# SD_Card_Led_Monitor.net
KiCad netlist of a schematic drawn in Altium Designer
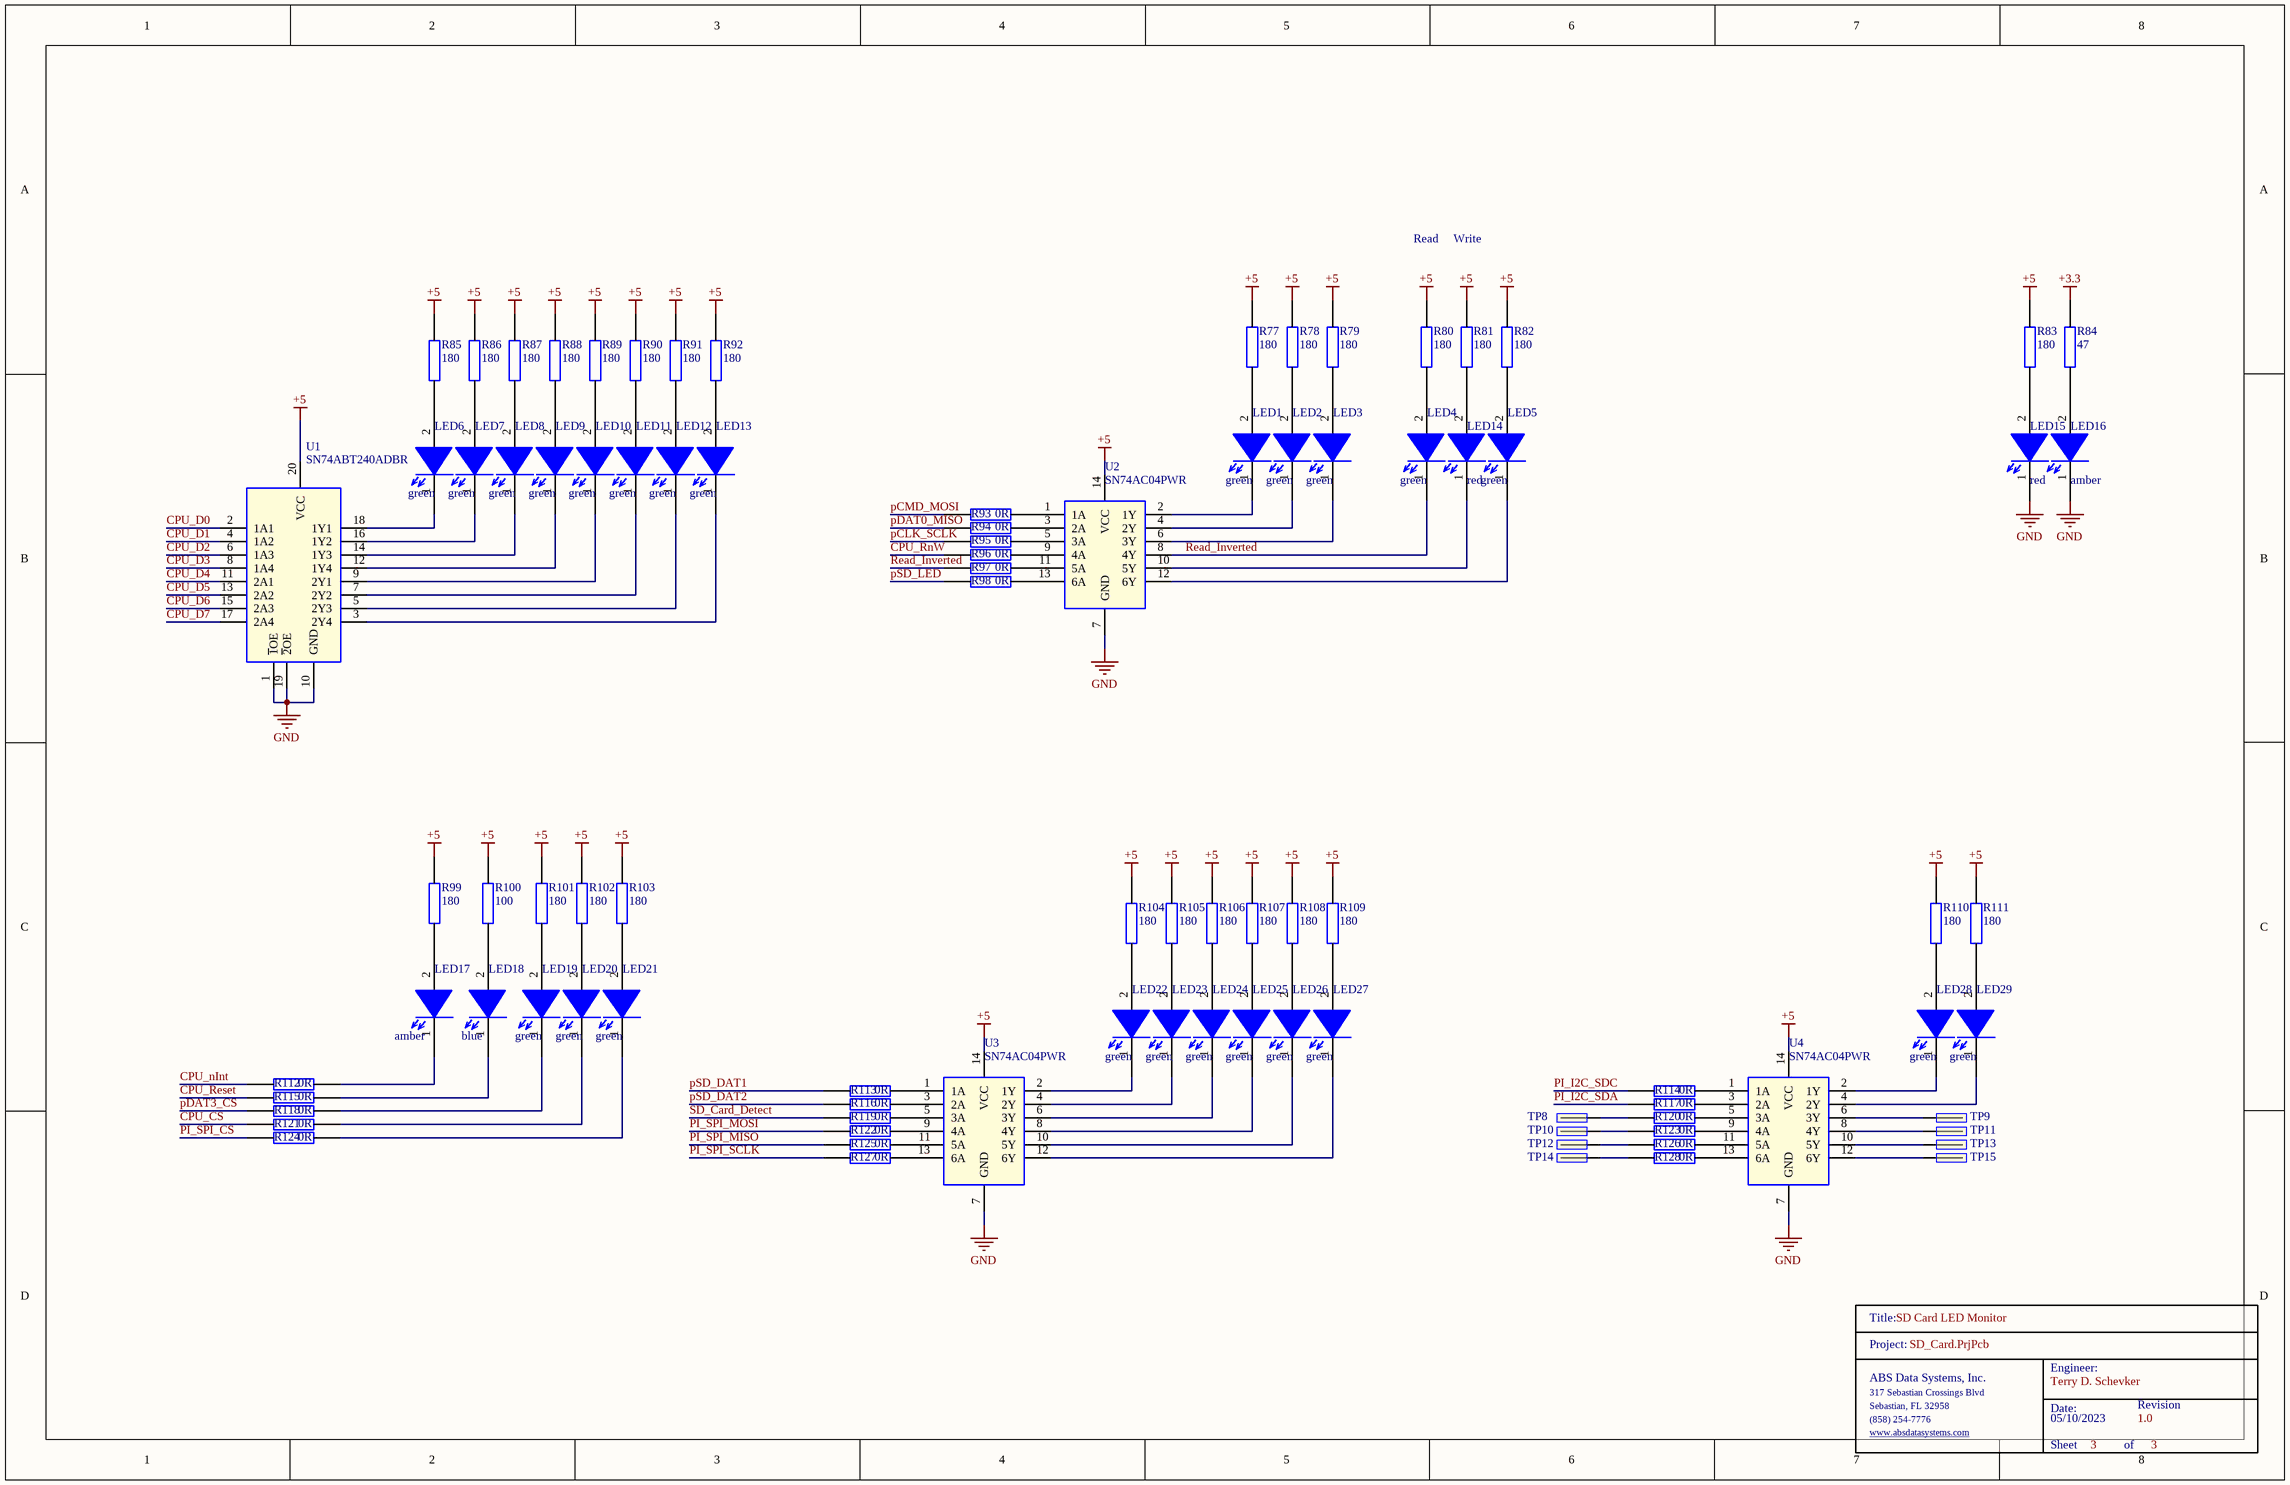
[diagram p0: SD_Card_Led_Monitor.SchDoc]

(export (version "E")
  (design (tool "Eeschema 10.0.6"))
  (components
    (comp (ref "LED1")
      (value "green")
      (footprint "0603_Diode")
      (description "Wurth Elektronik 0603 green")
      (fields
        (field (name "MANUFACTURER") "Wurth Electronics")
        (field (name "MANUFACTURER PART NUMBER") "150060GS75000")
      )
      (libsource (lib "Misc") (part "150060GS75000"))
    )
    (comp (ref "LED2")
      (value "green")
      (footprint "0603_Diode")
      (description "Wurth Elektronik 0603 green")
      (fields
        (field (name "MANUFACTURER") "Wurth Electronics")
        (field (name "MANUFACTURER PART NUMBER") "150060GS75000")
      )
      (libsource (lib "Misc") (part "150060GS75000"))
    )
    (comp (ref "LED3")
      (value "green")
      (footprint "0603_Diode")
      (description "Wurth Elektronik 0603 green")
      (fields
        (field (name "MANUFACTURER") "Wurth Electronics")
        (field (name "MANUFACTURER PART NUMBER") "150060GS75000")
      )
      (libsource (lib "Misc") (part "150060GS75000"))
    )
    (comp (ref "LED4")
      (value "green")
      (footprint "0603_Diode")
      (description "Wurth Elektronik 0603 green")
      (fields
        (field (name "MANUFACTURER") "Wurth Electronics")
        (field (name "MANUFACTURER PART NUMBER") "150060GS75000")
      )
      (libsource (lib "Misc") (part "150060GS75000"))
    )
    (comp (ref "LED5")
      (value "green")
      (footprint "0603_Diode")
      (description "Wurth Elektronik 0603 green")
      (fields
        (field (name "MANUFACTURER") "Wurth Electronics")
        (field (name "MANUFACTURER PART NUMBER") "150060GS75000")
      )
      (libsource (lib "Misc") (part "150060GS75000"))
    )
    (comp (ref "LED6")
      (value "green")
      (footprint "0603_Diode")
      (description "Wurth Elektronik 0603 green")
      (fields
        (field (name "MANUFACTURER") "Wurth Electronics")
        (field (name "MANUFACTURER PART NUMBER") "150060GS75000")
      )
      (libsource (lib "Misc") (part "150060GS75000"))
    )
    (comp (ref "LED7")
      (value "green")
      (footprint "0603_Diode")
      (description "Wurth Elektronik 0603 green")
      (fields
        (field (name "MANUFACTURER") "Wurth Electronics")
        (field (name "MANUFACTURER PART NUMBER") "150060GS75000")
      )
      (libsource (lib "Misc") (part "150060GS75000"))
    )
    (comp (ref "LED8")
      (value "green")
      (footprint "0603_Diode")
      (description "Wurth Elektronik 0603 green")
      (fields
        (field (name "MANUFACTURER") "Wurth Electronics")
        (field (name "MANUFACTURER PART NUMBER") "150060GS75000")
      )
      (libsource (lib "Misc") (part "150060GS75000"))
    )
    (comp (ref "LED9")
      (value "green")
      (footprint "0603_Diode")
      (description "Wurth Elektronik 0603 green")
      (fields
        (field (name "MANUFACTURER") "Wurth Electronics")
        (field (name "MANUFACTURER PART NUMBER") "150060GS75000")
      )
      (libsource (lib "Misc") (part "150060GS75000"))
    )
    (comp (ref "LED10")
      (value "green")
      (footprint "0603_Diode")
      (description "Wurth Elektronik 0603 green")
      (fields
        (field (name "MANUFACTURER") "Wurth Electronics")
        (field (name "MANUFACTURER PART NUMBER") "150060GS75000")
      )
      (libsource (lib "Misc") (part "150060GS75000"))
    )
    (comp (ref "LED11")
      (value "green")
      (footprint "0603_Diode")
      (description "Wurth Elektronik 0603 green")
      (fields
        (field (name "MANUFACTURER") "Wurth Electronics")
        (field (name "MANUFACTURER PART NUMBER") "150060GS75000")
      )
      (libsource (lib "Misc") (part "150060GS75000"))
    )
    (comp (ref "LED12")
      (value "green")
      (footprint "0603_Diode")
      (description "Wurth Elektronik 0603 green")
      (fields
        (field (name "MANUFACTURER") "Wurth Electronics")
        (field (name "MANUFACTURER PART NUMBER") "150060GS75000")
      )
      (libsource (lib "Misc") (part "150060GS75000"))
    )
    (comp (ref "LED13")
      (value "green")
      (footprint "0603_Diode")
      (description "Wurth Elektronik 0603 green")
      (fields
        (field (name "MANUFACTURER") "Wurth Electronics")
        (field (name "MANUFACTURER PART NUMBER") "150060GS75000")
      )
      (libsource (lib "Misc") (part "150060GS75000"))
    )
    (comp (ref "LED14")
      (value "red")
      (footprint "0603_Diode")
      (description "Wurth Elektronik 0603 red")
      (fields
        (field (name "MANUFACTURER") "Wurth Electronics")
        (field (name "MANUFACTURER PART NUMBER") "150060GS75000")
      )
      (libsource (lib "Misc") (part "150060RS75000"))
    )
    (comp (ref "LED15")
      (value "red")
      (footprint "0603_Diode")
      (description "Wurth Elektronik 0603 red")
      (fields
        (field (name "MANUFACTURER") "Wurth Electronics")
        (field (name "MANUFACTURER PART NUMBER") "150060GS75000")
      )
      (libsource (lib "Misc") (part "150060RS75000"))
    )
    (comp (ref "LED16")
      (value "amber")
      (footprint "0603_Diode")
      (description "Wurth Elektronik 0603 amber")
      (fields
        (field (name "MANUFACTURER") "Wurth Electronics")
        (field (name "MANUFACTURER PART NUMBER") "150060GS75000")
      )
      (libsource (lib "Misc") (part "150060AS75000"))
    )
    (comp (ref "LED17")
      (value "amber")
      (footprint "0603_Diode")
      (description "Wurth Elektronik 0603 amber")
      (fields
        (field (name "MANUFACTURER") "Wurth Electronics")
        (field (name "MANUFACTURER PART NUMBER") "150060GS75000")
      )
      (libsource (lib "Misc") (part "150060AS75000"))
    )
    (comp (ref "LED18")
      (value "blue")
      (footprint "0603_Diode")
      (description "Wurth Elektronik 0603 blue")
      (fields
        (field (name "MANUFACTURER") "Wurth Electronics")
        (field (name "MANUFACTURER PART NUMBER") "150060GS75000")
      )
      (libsource (lib "Misc") (part "150060BS75000"))
    )
    (comp (ref "LED19")
      (value "green")
      (footprint "0603_Diode")
      (description "Wurth Elektronik 0603 green")
      (fields
        (field (name "MANUFACTURER") "Wurth Electronics")
        (field (name "MANUFACTURER PART NUMBER") "150060GS75000")
      )
      (libsource (lib "Misc") (part "150060GS75000"))
    )
    (comp (ref "LED20")
      (value "green")
      (footprint "0603_Diode")
      (description "Wurth Elektronik 0603 green")
      (fields
        (field (name "MANUFACTURER") "Wurth Electronics")
        (field (name "MANUFACTURER PART NUMBER") "150060GS75000")
      )
      (libsource (lib "Misc") (part "150060GS75000"))
    )
    (comp (ref "LED21")
      (value "green")
      (footprint "0603_Diode")
      (description "Wurth Elektronik 0603 green")
      (fields
        (field (name "MANUFACTURER") "Wurth Electronics")
        (field (name "MANUFACTURER PART NUMBER") "150060GS75000")
      )
      (libsource (lib "Misc") (part "150060GS75000"))
    )
    (comp (ref "LED22")
      (value "green")
      (footprint "0603_Diode")
      (description "Wurth Elektronik 0603 green")
      (fields
        (field (name "MANUFACTURER") "Wurth Electronics")
        (field (name "MANUFACTURER PART NUMBER") "150060GS75000")
      )
      (libsource (lib "Misc") (part "150060GS75000"))
    )
    (comp (ref "LED23")
      (value "green")
      (footprint "0603_Diode")
      (description "Wurth Elektronik 0603 green")
      (fields
        (field (name "MANUFACTURER") "Wurth Electronics")
        (field (name "MANUFACTURER PART NUMBER") "150060GS75000")
      )
      (libsource (lib "Misc") (part "150060GS75000"))
    )
    (comp (ref "LED24")
      (value "green")
      (footprint "0603_Diode")
      (description "Wurth Elektronik 0603 green")
      (fields
        (field (name "MANUFACTURER") "Wurth Electronics")
        (field (name "MANUFACTURER PART NUMBER") "150060GS75000")
      )
      (libsource (lib "Misc") (part "150060GS75000"))
    )
    (comp (ref "LED25")
      (value "green")
      (footprint "0603_Diode")
      (description "Wurth Elektronik 0603 green")
      (fields
        (field (name "MANUFACTURER") "Wurth Electronics")
        (field (name "MANUFACTURER PART NUMBER") "150060GS75000")
      )
      (libsource (lib "Misc") (part "150060GS75000"))
    )
    (comp (ref "LED26")
      (value "green")
      (footprint "0603_Diode")
      (description "Wurth Elektronik 0603 green")
      (fields
        (field (name "MANUFACTURER") "Wurth Electronics")
        (field (name "MANUFACTURER PART NUMBER") "150060GS75000")
      )
      (libsource (lib "Misc") (part "150060GS75000"))
    )
    (comp (ref "LED27")
      (value "green")
      (footprint "0603_Diode")
      (description "Wurth Elektronik 0603 green")
      (fields
        (field (name "MANUFACTURER") "Wurth Electronics")
        (field (name "MANUFACTURER PART NUMBER") "150060GS75000")
      )
      (libsource (lib "Misc") (part "150060GS75000"))
    )
    (comp (ref "LED28")
      (value "green")
      (footprint "0603_Diode")
      (description "Wurth Elektronik 0603 green")
      (fields
        (field (name "MANUFACTURER") "Wurth Electronics")
        (field (name "MANUFACTURER PART NUMBER") "150060GS75000")
      )
      (libsource (lib "Misc") (part "150060GS75000"))
    )
    (comp (ref "LED29")
      (value "green")
      (footprint "0603_Diode")
      (description "Wurth Elektronik 0603 green")
      (fields
        (field (name "MANUFACTURER") "Wurth Electronics")
        (field (name "MANUFACTURER PART NUMBER") "150060GS75000")
      )
      (libsource (lib "Misc") (part "150060GS75000"))
    )
    (comp (ref "R77")
      (value "180")
      (footprint "0603")
      (description "YAGEO 0603 180 ohm")
      (fields
        (field (name "MOUSER PART NUMBER") "603-RC0603JR-070RL")
        (field (name "MANUFACTURER_PART_NUMBER") "RC0603JR-070RL")
      )
      (libsource (lib "Resistors") (part "RC0603FR-13180RL"))
    )
    (comp (ref "R78")
      (value "180")
      (footprint "0603")
      (description "YAGEO 0603 180 ohm")
      (fields
        (field (name "MOUSER PART NUMBER") "603-RC0603JR-070RL")
        (field (name "MANUFACTURER_PART_NUMBER") "RC0603JR-070RL")
      )
      (libsource (lib "Resistors") (part "RC0603FR-13180RL"))
    )
    (comp (ref "R79")
      (value "180")
      (footprint "0603")
      (description "YAGEO 0603 180 ohm")
      (fields
        (field (name "MOUSER PART NUMBER") "603-RC0603JR-070RL")
        (field (name "MANUFACTURER_PART_NUMBER") "RC0603JR-070RL")
      )
      (libsource (lib "Resistors") (part "RC0603FR-13180RL"))
    )
    (comp (ref "R80")
      (value "180")
      (footprint "0603")
      (description "YAGEO 0603 180 ohm")
      (fields
        (field (name "MOUSER PART NUMBER") "603-RC0603JR-070RL")
        (field (name "MANUFACTURER_PART_NUMBER") "RC0603JR-070RL")
      )
      (libsource (lib "Resistors") (part "RC0603FR-13180RL"))
    )
    (comp (ref "R81")
      (value "180")
      (footprint "0603")
      (description "YAGEO 0603 180 ohm")
      (fields
        (field (name "MOUSER PART NUMBER") "603-RC0603JR-070RL")
        (field (name "MANUFACTURER_PART_NUMBER") "RC0603JR-070RL")
      )
      (libsource (lib "Resistors") (part "RC0603FR-13180RL"))
    )
    (comp (ref "R82")
      (value "180")
      (footprint "0603")
      (description "YAGEO 0603 180 ohm")
      (fields
        (field (name "MOUSER PART NUMBER") "603-RC0603JR-070RL")
        (field (name "MANUFACTURER_PART_NUMBER") "RC0603JR-070RL")
      )
      (libsource (lib "Resistors") (part "RC0603FR-13180RL"))
    )
    (comp (ref "R83")
      (value "180")
      (footprint "0603")
      (description "YAGEO 0603 180 ohm")
      (fields
        (field (name "MOUSER PART NUMBER") "603-RC0603JR-070RL")
        (field (name "MANUFACTURER_PART_NUMBER") "RC0603JR-070RL")
      )
      (libsource (lib "Resistors") (part "RC0603FR-13180RL"))
    )
    (comp (ref "R84")
      (value "47")
      (footprint "0603")
      (description "YAGEO 0603 47")
      (fields
        (field (name "MOUSER PART NUMBER") "603-RC0603JR-070RL")
        (field (name "MANUFACTURER_PART_NUMBER") "RC0603JR-070RL")
      )
      (libsource (lib "Resistors") (part "RC0603FR-0747KL"))
    )
    (comp (ref "R85")
      (value "180")
      (footprint "0603")
      (description "YAGEO 0603 180 ohm")
      (fields
        (field (name "MOUSER PART NUMBER") "603-RC0603JR-070RL")
        (field (name "MANUFACTURER_PART_NUMBER") "RC0603JR-070RL")
      )
      (libsource (lib "Resistors") (part "RC0603FR-13180RL"))
    )
    (comp (ref "R86")
      (value "180")
      (footprint "0603")
      (description "YAGEO 0603 180 ohm")
      (fields
        (field (name "MOUSER PART NUMBER") "603-RC0603JR-070RL")
        (field (name "MANUFACTURER_PART_NUMBER") "RC0603JR-070RL")
      )
      (libsource (lib "Resistors") (part "RC0603FR-13180RL"))
    )
    (comp (ref "R87")
      (value "180")
      (footprint "0603")
      (description "YAGEO 0603 180 ohm")
      (fields
        (field (name "MOUSER PART NUMBER") "603-RC0603JR-070RL")
        (field (name "MANUFACTURER_PART_NUMBER") "RC0603JR-070RL")
      )
      (libsource (lib "Resistors") (part "RC0603FR-13180RL"))
    )
    (comp (ref "R88")
      (value "180")
      (footprint "0603")
      (description "YAGEO 0603 180 ohm")
      (fields
        (field (name "MOUSER PART NUMBER") "603-RC0603JR-070RL")
        (field (name "MANUFACTURER_PART_NUMBER") "RC0603JR-070RL")
      )
      (libsource (lib "Resistors") (part "RC0603FR-13180RL"))
    )
    (comp (ref "R89")
      (value "180")
      (footprint "0603")
      (description "YAGEO 0603 180 ohm")
      (fields
        (field (name "MOUSER PART NUMBER") "603-RC0603JR-070RL")
        (field (name "MANUFACTURER_PART_NUMBER") "RC0603JR-070RL")
      )
      (libsource (lib "Resistors") (part "RC0603FR-13180RL"))
    )
    (comp (ref "R90")
      (value "180")
      (footprint "0603")
      (description "YAGEO 0603 180 ohm")
      (fields
        (field (name "MOUSER PART NUMBER") "603-RC0603JR-070RL")
        (field (name "MANUFACTURER_PART_NUMBER") "RC0603JR-070RL")
      )
      (libsource (lib "Resistors") (part "RC0603FR-13180RL"))
    )
    (comp (ref "R91")
      (value "180")
      (footprint "0603")
      (description "YAGEO 0603 180 ohm")
      (fields
        (field (name "MOUSER PART NUMBER") "603-RC0603JR-070RL")
        (field (name "MANUFACTURER_PART_NUMBER") "RC0603JR-070RL")
      )
      (libsource (lib "Resistors") (part "RC0603FR-13180RL"))
    )
    (comp (ref "R92")
      (value "180")
      (footprint "0603")
      (description "YAGEO 0603 180 ohm")
      (fields
        (field (name "MOUSER PART NUMBER") "603-RC0603JR-070RL")
        (field (name "MANUFACTURER_PART_NUMBER") "RC0603JR-070RL")
      )
      (libsource (lib "Resistors") (part "RC0603FR-13180RL"))
    )
    (comp (ref "R93")
      (value "0R")
      (footprint "0603")
      (description "YAGEO 0603 0 ohm")
      (fields
        (field (name "MOUSER PART NUMBER") "603-RC0603JR-070RL")
        (field (name "MANUFACTURER_PART_NUMBER") "RC0603JR-070RL")
      )
      (libsource (lib "Resistors") (part "RC0603JR-070RL"))
    )
    (comp (ref "R94")
      (value "0R")
      (footprint "0603")
      (description "YAGEO 0603 0 ohm")
      (fields
        (field (name "MOUSER PART NUMBER") "603-RC0603JR-070RL")
        (field (name "MANUFACTURER_PART_NUMBER") "RC0603JR-070RL")
      )
      (libsource (lib "Resistors") (part "RC0603JR-070RL"))
    )
    (comp (ref "R95")
      (value "0R")
      (footprint "0603")
      (description "YAGEO 0603 0 ohm")
      (fields
        (field (name "MOUSER PART NUMBER") "603-RC0603JR-070RL")
        (field (name "MANUFACTURER_PART_NUMBER") "RC0603JR-070RL")
      )
      (libsource (lib "Resistors") (part "RC0603JR-070RL"))
    )
    (comp (ref "R96")
      (value "0R")
      (footprint "0603")
      (description "YAGEO 0603 0 ohm")
      (fields
        (field (name "MOUSER PART NUMBER") "603-RC0603JR-070RL")
        (field (name "MANUFACTURER_PART_NUMBER") "RC0603JR-070RL")
      )
      (libsource (lib "Resistors") (part "RC0603JR-070RL"))
    )
    (comp (ref "R97")
      (value "0R")
      (footprint "0603")
      (description "YAGEO 0603 0 ohm")
      (fields
        (field (name "MOUSER PART NUMBER") "603-RC0603JR-070RL")
        (field (name "MANUFACTURER_PART_NUMBER") "RC0603JR-070RL")
      )
      (libsource (lib "Resistors") (part "RC0603JR-070RL"))
    )
    (comp (ref "R98")
      (value "0R")
      (footprint "0603")
      (description "YAGEO 0603 0 ohm")
      (fields
        (field (name "MOUSER PART NUMBER") "603-RC0603JR-070RL")
        (field (name "MANUFACTURER_PART_NUMBER") "RC0603JR-070RL")
      )
      (libsource (lib "Resistors") (part "RC0603JR-070RL"))
    )
    (comp (ref "R99")
      (value "180")
      (footprint "0603")
      (description "YAGEO 0603 180 ohm")
      (fields
        (field (name "MOUSER PART NUMBER") "603-RC0603JR-070RL")
        (field (name "MANUFACTURER_PART_NUMBER") "RC0603JR-070RL")
      )
      (libsource (lib "Resistors") (part "RC0603FR-13180RL"))
    )
    (comp (ref "R100")
      (value "100")
      (footprint "0603")
      (description "YAGEO 0603 100 ohm")
      (fields
        (field (name "MOUSER PART NUMBER") "603-RC0603JR-070RL")
        (field (name "MANUFACTURER_PART_NUMBER") "RC0603JR-070RL")
      )
      (libsource (lib "Resistors") (part "RC0603FR-10100RL"))
    )
    (comp (ref "R101")
      (value "180")
      (footprint "0603")
      (description "YAGEO 0603 180 ohm")
      (fields
        (field (name "MOUSER PART NUMBER") "603-RC0603JR-070RL")
        (field (name "MANUFACTURER_PART_NUMBER") "RC0603JR-070RL")
      )
      (libsource (lib "Resistors") (part "RC0603FR-13180RL"))
    )
    (comp (ref "R102")
      (value "180")
      (footprint "0603")
      (description "YAGEO 0603 180 ohm")
      (fields
        (field (name "MOUSER PART NUMBER") "603-RC0603JR-070RL")
        (field (name "MANUFACTURER_PART_NUMBER") "RC0603JR-070RL")
      )
      (libsource (lib "Resistors") (part "RC0603FR-13180RL"))
    )
    (comp (ref "R103")
      (value "180")
      (footprint "0603")
      (description "YAGEO 0603 180 ohm")
      (fields
        (field (name "MOUSER PART NUMBER") "603-RC0603JR-070RL")
        (field (name "MANUFACTURER_PART_NUMBER") "RC0603JR-070RL")
      )
      (libsource (lib "Resistors") (part "RC0603FR-13180RL"))
    )
    (comp (ref "R104")
      (value "180")
      (footprint "0603")
      (description "YAGEO 0603 180 ohm")
      (fields
        (field (name "MOUSER PART NUMBER") "603-RC0603JR-070RL")
        (field (name "MANUFACTURER_PART_NUMBER") "RC0603JR-070RL")
      )
      (libsource (lib "Resistors") (part "RC0603FR-13180RL"))
    )
    (comp (ref "R105")
      (value "180")
      (footprint "0603")
      (description "YAGEO 0603 180 ohm")
      (fields
        (field (name "MOUSER PART NUMBER") "603-RC0603JR-070RL")
        (field (name "MANUFACTURER_PART_NUMBER") "RC0603JR-070RL")
      )
      (libsource (lib "Resistors") (part "RC0603FR-13180RL"))
    )
    (comp (ref "R106")
      (value "180")
      (footprint "0603")
      (description "YAGEO 0603 180 ohm")
      (fields
        (field (name "MOUSER PART NUMBER") "603-RC0603JR-070RL")
        (field (name "MANUFACTURER_PART_NUMBER") "RC0603JR-070RL")
      )
      (libsource (lib "Resistors") (part "RC0603FR-13180RL"))
    )
    (comp (ref "R107")
      (value "180")
      (footprint "0603")
      (description "YAGEO 0603 180 ohm")
      (fields
        (field (name "MOUSER PART NUMBER") "603-RC0603JR-070RL")
        (field (name "MANUFACTURER_PART_NUMBER") "RC0603JR-070RL")
      )
      (libsource (lib "Resistors") (part "RC0603FR-13180RL"))
    )
    (comp (ref "R108")
      (value "180")
      (footprint "0603")
      (description "YAGEO 0603 180 ohm")
      (fields
        (field (name "MOUSER PART NUMBER") "603-RC0603JR-070RL")
        (field (name "MANUFACTURER_PART_NUMBER") "RC0603JR-070RL")
      )
      (libsource (lib "Resistors") (part "RC0603FR-13180RL"))
    )
    (comp (ref "R109")
      (value "180")
      (footprint "0603")
      (description "YAGEO 0603 180 ohm")
      (fields
        (field (name "MOUSER PART NUMBER") "603-RC0603JR-070RL")
        (field (name "MANUFACTURER_PART_NUMBER") "RC0603JR-070RL")
      )
      (libsource (lib "Resistors") (part "RC0603FR-13180RL"))
    )
    (comp (ref "R110")
      (value "180")
      (footprint "0603")
      (description "YAGEO 0603 180 ohm")
      (fields
        (field (name "MOUSER PART NUMBER") "603-RC0603JR-070RL")
        (field (name "MANUFACTURER_PART_NUMBER") "RC0603JR-070RL")
      )
      (libsource (lib "Resistors") (part "RC0603FR-13180RL"))
    )
    (comp (ref "R111")
      (value "180")
      (footprint "0603")
      (description "YAGEO 0603 180 ohm")
      (fields
        (field (name "MOUSER PART NUMBER") "603-RC0603JR-070RL")
        (field (name "MANUFACTURER_PART_NUMBER") "RC0603JR-070RL")
      )
      (libsource (lib "Resistors") (part "RC0603FR-13180RL"))
    )
    (comp (ref "R112")
      (value "0R")
      (footprint "0603")
      (description "YAGEO 0603 0 ohm")
      (fields
        (field (name "MOUSER PART NUMBER") "603-RC0603JR-070RL")
        (field (name "MANUFACTURER_PART_NUMBER") "RC0603JR-070RL")
      )
      (libsource (lib "Resistors") (part "RC0603JR-070RL"))
    )
    (comp (ref "R113")
      (value "0R")
      (footprint "0603")
      (description "YAGEO 0603 0 ohm")
      (fields
        (field (name "MOUSER PART NUMBER") "603-RC0603JR-070RL")
        (field (name "MANUFACTURER_PART_NUMBER") "RC0603JR-070RL")
      )
      (libsource (lib "Resistors") (part "RC0603JR-070RL"))
    )
    (comp (ref "R114")
      (value "0R")
      (footprint "0603")
      (description "YAGEO 0603 0 ohm")
      (fields
        (field (name "MOUSER PART NUMBER") "603-RC0603JR-070RL")
        (field (name "MANUFACTURER_PART_NUMBER") "RC0603JR-070RL")
      )
      (libsource (lib "Resistors") (part "RC0603JR-070RL"))
    )
    (comp (ref "R115")
      (value "0R")
      (footprint "0603")
      (description "YAGEO 0603 0 ohm")
      (fields
        (field (name "MOUSER PART NUMBER") "603-RC0603JR-070RL")
        (field (name "MANUFACTURER_PART_NUMBER") "RC0603JR-070RL")
      )
      (libsource (lib "Resistors") (part "RC0603JR-070RL"))
    )
    (comp (ref "R116")
      (value "0R")
      (footprint "0603")
      (description "YAGEO 0603 0 ohm")
      (fields
        (field (name "MOUSER PART NUMBER") "603-RC0603JR-070RL")
        (field (name "MANUFACTURER_PART_NUMBER") "RC0603JR-070RL")
      )
      (libsource (lib "Resistors") (part "RC0603JR-070RL"))
    )
    (comp (ref "R117")
      (value "0R")
      (footprint "0603")
      (description "YAGEO 0603 0 ohm")
      (fields
        (field (name "MOUSER PART NUMBER") "603-RC0603JR-070RL")
        (field (name "MANUFACTURER_PART_NUMBER") "RC0603JR-070RL")
      )
      (libsource (lib "Resistors") (part "RC0603JR-070RL"))
    )
    (comp (ref "R118")
      (value "0R")
      (footprint "0603")
      (description "YAGEO 0603 0 ohm")
      (fields
        (field (name "MOUSER PART NUMBER") "603-RC0603JR-070RL")
        (field (name "MANUFACTURER_PART_NUMBER") "RC0603JR-070RL")
      )
      (libsource (lib "Resistors") (part "RC0603JR-070RL"))
    )
    (comp (ref "R119")
      (value "0R")
      (footprint "0603")
      (description "YAGEO 0603 0 ohm")
      (fields
        (field (name "MOUSER PART NUMBER") "603-RC0603JR-070RL")
        (field (name "MANUFACTURER_PART_NUMBER") "RC0603JR-070RL")
      )
      (libsource (lib "Resistors") (part "RC0603JR-070RL"))
    )
    (comp (ref "R120")
      (value "0R")
      (footprint "0603")
      (description "YAGEO 0603 0 ohm")
      (fields
        (field (name "MOUSER PART NUMBER") "603-RC0603JR-070RL")
        (field (name "MANUFACTURER_PART_NUMBER") "RC0603JR-070RL")
      )
      (libsource (lib "Resistors") (part "RC0603JR-070RL"))
    )
    (comp (ref "R121")
      (value "0R")
      (footprint "0603")
      (description "YAGEO 0603 0 ohm")
      (fields
        (field (name "MOUSER PART NUMBER") "603-RC0603JR-070RL")
        (field (name "MANUFACTURER_PART_NUMBER") "RC0603JR-070RL")
      )
      (libsource (lib "Resistors") (part "RC0603JR-070RL"))
    )
    (comp (ref "R122")
      (value "0R")
      (footprint "0603")
      (description "YAGEO 0603 0 ohm")
      (fields
        (field (name "MOUSER PART NUMBER") "603-RC0603JR-070RL")
        (field (name "MANUFACTURER_PART_NUMBER") "RC0603JR-070RL")
      )
      (libsource (lib "Resistors") (part "RC0603JR-070RL"))
    )
    (comp (ref "R123")
      (value "0R")
      (footprint "0603")
      (description "YAGEO 0603 0 ohm")
      (fields
        (field (name "MOUSER PART NUMBER") "603-RC0603JR-070RL")
        (field (name "MANUFACTURER_PART_NUMBER") "RC0603JR-070RL")
      )
      (libsource (lib "Resistors") (part "RC0603JR-070RL"))
    )
    (comp (ref "R124")
      (value "0R")
      (footprint "0603")
      (description "YAGEO 0603 0 ohm")
      (fields
        (field (name "MOUSER PART NUMBER") "603-RC0603JR-070RL")
        (field (name "MANUFACTURER_PART_NUMBER") "RC0603JR-070RL")
      )
      (libsource (lib "Resistors") (part "RC0603JR-070RL"))
    )
    (comp (ref "R125")
      (value "0R")
      (footprint "0603")
      (description "YAGEO 0603 0 ohm")
      (fields
        (field (name "MOUSER PART NUMBER") "603-RC0603JR-070RL")
        (field (name "MANUFACTURER_PART_NUMBER") "RC0603JR-070RL")
      )
      (libsource (lib "Resistors") (part "RC0603JR-070RL"))
    )
    (comp (ref "R126")
      (value "0R")
      (footprint "0603")
      (description "YAGEO 0603 0 ohm")
      (fields
        (field (name "MOUSER PART NUMBER") "603-RC0603JR-070RL")
        (field (name "MANUFACTURER_PART_NUMBER") "RC0603JR-070RL")
      )
      (libsource (lib "Resistors") (part "RC0603JR-070RL"))
    )
    (comp (ref "R127")
      (value "0R")
      (footprint "0603")
      (description "YAGEO 0603 0 ohm")
      (fields
        (field (name "MOUSER PART NUMBER") "603-RC0603JR-070RL")
        (field (name "MANUFACTURER_PART_NUMBER") "RC0603JR-070RL")
      )
      (libsource (lib "Resistors") (part "RC0603JR-070RL"))
    )
    (comp (ref "R128")
      (value "0R")
      (footprint "0603")
      (description "YAGEO 0603 0 ohm")
      (fields
        (field (name "MOUSER PART NUMBER") "603-RC0603JR-070RL")
        (field (name "MANUFACTURER_PART_NUMBER") "RC0603JR-070RL")
      )
      (libsource (lib "Resistors") (part "RC0603JR-070RL"))
    )
    (comp (ref "TitleBlock_3") (value "TitleBlock") (libsource (lib "Misc") (part "TitleBlock")))
    (comp (ref "TP8")
      (value "TP")
      (footprint "TP")
      (fields
        (field (name "MANUFACTURER") "Samtec")
        (field (name "MANUFACTURER PART NUMBER") "TST-105-01-G-D")
      )
      (libsource (lib "") (part "TP_1"))
    )
    (comp (ref "TP9")
      (value "TP")
      (footprint "TP")
      (fields
        (field (name "MANUFACTURER") "Samtec")
        (field (name "MANUFACTURER PART NUMBER") "TST-105-01-G-D")
      )
      (libsource (lib "Misc") (part "TP"))
    )
    (comp (ref "TP10")
      (value "TP")
      (footprint "TP")
      (fields
        (field (name "MANUFACTURER") "Samtec")
        (field (name "MANUFACTURER PART NUMBER") "TST-105-01-G-D")
      )
      (libsource (lib "") (part "TP_1"))
    )
    (comp (ref "TP11")
      (value "TP")
      (footprint "TP")
      (fields
        (field (name "MANUFACTURER") "Samtec")
        (field (name "MANUFACTURER PART NUMBER") "TST-105-01-G-D")
      )
      (libsource (lib "Misc") (part "TP"))
    )
    (comp (ref "TP12")
      (value "TP")
      (footprint "TP")
      (fields
        (field (name "MANUFACTURER") "Samtec")
        (field (name "MANUFACTURER PART NUMBER") "TST-105-01-G-D")
      )
      (libsource (lib "") (part "TP_1"))
    )
    (comp (ref "TP13")
      (value "TP")
      (footprint "TP")
      (fields
        (field (name "MANUFACTURER") "Samtec")
        (field (name "MANUFACTURER PART NUMBER") "TST-105-01-G-D")
      )
      (libsource (lib "Misc") (part "TP"))
    )
    (comp (ref "TP14")
      (value "TP")
      (footprint "TP")
      (fields
        (field (name "MANUFACTURER") "Samtec")
        (field (name "MANUFACTURER PART NUMBER") "TST-105-01-G-D")
      )
      (libsource (lib "") (part "TP_1"))
    )
    (comp (ref "TP15")
      (value "TP")
      (footprint "TP")
      (fields
        (field (name "MANUFACTURER") "Samtec")
        (field (name "MANUFACTURER PART NUMBER") "TST-105-01-G-D")
      )
      (libsource (lib "Misc") (part "TP"))
    )
    (comp (ref "U1")
      (value "SN74ABT240ADBR")
      (footprint "SOP65P780X200-20N")
      (description "Octal Buffers/Drivers With 3-State Outputs")
      (fields (field (name "MOUSER PART NUMBER") "595-SN74ABT240ADBR"))
      (libsource (lib "Logic") (part "SN74ABT240ADBR"))
    )
    (comp (ref "U2")
      (value "SN74AC04PWR")
      (footprint "SOP65P640X120-14N")
      (description "Hex Inverters")
      (fields (field (name "MOUSER PART NUMBER") "595-SN74AC04PWR"))
      (libsource (lib "Logic") (part "SN74AC04PWR"))
    )
    (comp (ref "U3")
      (value "SN74AC04PWR")
      (footprint "SOP65P640X120-14N")
      (description "Hex Inverters")
      (fields (field (name "MOUSER PART NUMBER") "595-SN74AC04PWR"))
      (libsource (lib "Logic") (part "SN74AC04PWR"))
    )
    (comp (ref "U4")
      (value "SN74AC04PWR")
      (footprint "SOP65P640X120-14N")
      (description "Hex Inverters")
      (fields (field (name "MOUSER PART NUMBER") "595-SN74AC04PWR"))
      (libsource (lib "Logic") (part "SN74AC04PWR"))
    )
  )
  (nets
    (net (code "1") (name "+3.3") (class "Default")
      (node (ref "R84") (pin "1") (pinfunction "1_1") (pintype "passive"))
    )
    (net (code "2") (name "+5") (class "Default")
      (node (ref "R100") (pin "1") (pinfunction "1_1") (pintype "passive"))
      (node (ref "R101") (pin "2") (pinfunction "2_2") (pintype "passive"))
      (node (ref "R102") (pin "2") (pinfunction "2_2") (pintype "passive"))
      (node (ref "R103") (pin "2") (pinfunction "2_2") (pintype "passive"))
      (node (ref "R104") (pin "2") (pinfunction "2_2") (pintype "passive"))
      (node (ref "R105") (pin "2") (pinfunction "2_2") (pintype "passive"))
      (node (ref "R106") (pin "2") (pinfunction "2_2") (pintype "passive"))
      (node (ref "R107") (pin "2") (pinfunction "2_2") (pintype "passive"))
      (node (ref "R108") (pin "2") (pinfunction "2_2") (pintype "passive"))
      (node (ref "R109") (pin "2") (pinfunction "2_2") (pintype "passive"))
      (node (ref "R110") (pin "2") (pinfunction "2_2") (pintype "passive"))
      (node (ref "R111") (pin "2") (pinfunction "2_2") (pintype "passive"))
      (node (ref "R77") (pin "2") (pinfunction "2_2") (pintype "passive"))
      (node (ref "R78") (pin "2") (pinfunction "2_2") (pintype "passive"))
      (node (ref "R79") (pin "2") (pinfunction "2_2") (pintype "passive"))
      (node (ref "R80") (pin "2") (pinfunction "2_2") (pintype "passive"))
      (node (ref "R81") (pin "2") (pinfunction "2_2") (pintype "passive"))
      (node (ref "R82") (pin "2") (pinfunction "2_2") (pintype "passive"))
      (node (ref "R83") (pin "2") (pinfunction "2_2") (pintype "passive"))
      (node (ref "R85") (pin "2") (pinfunction "2_2") (pintype "passive"))
      (node (ref "R86") (pin "2") (pinfunction "2_2") (pintype "passive"))
      (node (ref "R87") (pin "2") (pinfunction "2_2") (pintype "passive"))
      (node (ref "R88") (pin "2") (pinfunction "2_2") (pintype "passive"))
      (node (ref "R89") (pin "2") (pinfunction "2_2") (pintype "passive"))
      (node (ref "R90") (pin "2") (pinfunction "2_2") (pintype "passive"))
      (node (ref "R91") (pin "2") (pinfunction "2_2") (pintype "passive"))
      (node (ref "R92") (pin "2") (pinfunction "2_2") (pintype "passive"))
      (node (ref "R99") (pin "2") (pinfunction "2_2") (pintype "passive"))
      (node (ref "U1") (pin "20") (pinfunction "VCC_20") (pintype "passive"))
      (node (ref "U2") (pin "14") (pinfunction "VCC_14") (pintype "passive"))
      (node (ref "U3") (pin "14") (pinfunction "VCC_14") (pintype "passive"))
      (node (ref "U4") (pin "14") (pinfunction "VCC_14") (pintype "passive"))
    )
    (net (code "3") (name "/CPU_CS") (class "Default")
      (node (ref "R121") (pin "1") (pinfunction "1_1") (pintype "passive"))
    )
    (net (code "4") (name "/CPU_D0") (class "Default")
      (node (ref "U1") (pin "2") (pinfunction "1A1_2") (pintype "passive"))
    )
    (net (code "5") (name "/CPU_D1") (class "Default")
      (node (ref "U1") (pin "4") (pinfunction "1A2_4") (pintype "passive"))
    )
    (net (code "6") (name "/CPU_D2") (class "Default")
      (node (ref "U1") (pin "6") (pinfunction "1A3_6") (pintype "passive"))
    )
    (net (code "7") (name "/CPU_D3") (class "Default")
      (node (ref "U1") (pin "8") (pinfunction "1A4_8") (pintype "passive"))
    )
    (net (code "8") (name "/CPU_D4") (class "Default")
      (node (ref "U1") (pin "11") (pinfunction "2A1_11") (pintype "passive"))
    )
    (net (code "9") (name "/CPU_D5") (class "Default")
      (node (ref "U1") (pin "13") (pinfunction "2A2_13") (pintype "passive"))
    )
    (net (code "10") (name "/CPU_D6") (class "Default")
      (node (ref "U1") (pin "15") (pinfunction "2A3_15") (pintype "passive"))
    )
    (net (code "11") (name "/CPU_D7") (class "Default")
      (node (ref "U1") (pin "17") (pinfunction "2A4_17") (pintype "passive"))
    )
    (net (code "12") (name "/CPU_Reset") (class "Default")
      (node (ref "R115") (pin "1") (pinfunction "1_1") (pintype "passive"))
    )
    (net (code "13") (name "/CPU_RnW") (class "Default")
      (node (ref "R96") (pin "1") (pinfunction "1_1") (pintype "passive"))
    )
    (net (code "14") (name "/CPU_nInt") (class "Default")
      (node (ref "R112") (pin "1") (pinfunction "1_1") (pintype "passive"))
    )
    (net (code "15") (name "/PI_I2C_SDA") (class "Default")
      (node (ref "R117") (pin "1") (pinfunction "1_1") (pintype "passive"))
    )
    (net (code "16") (name "/PI_I2C_SDC") (class "Default")
      (node (ref "R114") (pin "1") (pinfunction "1_1") (pintype "passive"))
    )
    (net (code "17") (name "/PI_SPI_CS") (class "Default")
      (node (ref "R124") (pin "1") (pinfunction "1_1") (pintype "passive"))
    )
    (net (code "18") (name "/PI_SPI_MISO") (class "Default")
      (node (ref "R125") (pin "1") (pinfunction "1_1") (pintype "passive"))
    )
    (net (code "19") (name "/PI_SPI_MOSI") (class "Default")
      (node (ref "R122") (pin "1") (pinfunction "1_1") (pintype "passive"))
    )
    (net (code "20") (name "/PI_SPI_SCLK") (class "Default")
      (node (ref "R127") (pin "1") (pinfunction "1_1") (pintype "passive"))
    )
    (net (code "21") (name "/Read_Inverted") (class "Default")
      (node (ref "LED4") (pin "1") (pinfunction "K_1") (pintype "passive"))
      (node (ref "R97") (pin "1") (pinfunction "1_1") (pintype "passive"))
      (node (ref "U2") (pin "8") (pinfunction "4Y_8") (pintype "passive"))
    )
    (net (code "22") (name "/SD_Card_Detect") (class "Default")
      (node (ref "R119") (pin "1") (pinfunction "1_1") (pintype "passive"))
    )
    (net (code "23") (name "/pCLK_SCLK") (class "Default")
      (node (ref "R95") (pin "1") (pinfunction "1_1") (pintype "passive"))
    )
    (net (code "24") (name "/pCMD_MOSI") (class "Default")
      (node (ref "R93") (pin "1") (pinfunction "1_1") (pintype "passive"))
    )
    (net (code "25") (name "/pDAT0_MISO") (class "Default")
      (node (ref "R94") (pin "1") (pinfunction "1_1") (pintype "passive"))
    )
    (net (code "26") (name "/pDAT3_CS") (class "Default")
      (node (ref "R118") (pin "1") (pinfunction "1_1") (pintype "passive"))
    )
    (net (code "27") (name "/pSD_DAT1") (class "Default")
      (node (ref "R113") (pin "1") (pinfunction "1_1") (pintype "passive"))
    )
    (net (code "28") (name "/pSD_DAT2") (class "Default")
      (node (ref "R116") (pin "1") (pinfunction "1_1") (pintype "passive"))
    )
    (net (code "29") (name "/pSD_LED") (class "Default")
      (node (ref "R98") (pin "1") (pinfunction "1_1") (pintype "passive"))
    )
    (net (code "30") (name "GND") (class "Default")
      (node (ref "LED15") (pin "1") (pinfunction "K_1") (pintype "passive"))
      (node (ref "LED16") (pin "1") (pinfunction "K_1") (pintype "passive"))
      (node (ref "U1") (pin "1") (pinfunction "~{1}OE_1") (pintype "passive"))
      (node (ref "U1") (pin "10") (pinfunction "GND_10") (pintype "passive"))
      (node (ref "U1") (pin "19") (pinfunction "~{2}OE_19") (pintype "passive"))
      (node (ref "U2") (pin "7") (pinfunction "GND_7") (pintype "passive"))
      (node (ref "U3") (pin "7") (pinfunction "GND_7") (pintype "passive"))
      (node (ref "U4") (pin "7") (pinfunction "GND_7") (pintype "passive"))
    )
    (net (code "31") (name "Net-(LED1-A)") (class "Default")
      (node (ref "LED1") (pin "2") (pinfunction "A_2") (pintype "passive"))
      (node (ref "R77") (pin "1") (pinfunction "1_1") (pintype "passive"))
    )
    (net (code "32") (name "Net-(LED1-K)") (class "Default")
      (node (ref "LED1") (pin "1") (pinfunction "K_1") (pintype "passive"))
      (node (ref "U2") (pin "2") (pinfunction "1Y_2") (pintype "passive"))
    )
    (net (code "33") (name "Net-(LED2-A)") (class "Default")
      (node (ref "LED2") (pin "2") (pinfunction "A_2") (pintype "passive"))
      (node (ref "R78") (pin "1") (pinfunction "1_1") (pintype "passive"))
    )
    (net (code "34") (name "Net-(LED2-K)") (class "Default")
      (node (ref "LED2") (pin "1") (pinfunction "K_1") (pintype "passive"))
      (node (ref "U2") (pin "4") (pinfunction "2Y_4") (pintype "passive"))
    )
    (net (code "35") (name "Net-(LED3-A)") (class "Default")
      (node (ref "LED3") (pin "2") (pinfunction "A_2") (pintype "passive"))
      (node (ref "R79") (pin "1") (pinfunction "1_1") (pintype "passive"))
    )
    (net (code "36") (name "Net-(LED3-K)") (class "Default")
      (node (ref "LED3") (pin "1") (pinfunction "K_1") (pintype "passive"))
      (node (ref "U2") (pin "6") (pinfunction "3Y_6") (pintype "passive"))
    )
    (net (code "37") (name "Net-(LED4-A)") (class "Default")
      (node (ref "LED4") (pin "2") (pinfunction "A_2") (pintype "passive"))
      (node (ref "R80") (pin "1") (pinfunction "1_1") (pintype "passive"))
    )
    (net (code "38") (name "Net-(LED5-A)") (class "Default")
      (node (ref "LED5") (pin "2") (pinfunction "A_2") (pintype "passive"))
      (node (ref "R82") (pin "1") (pinfunction "1_1") (pintype "passive"))
    )
    (net (code "39") (name "Net-(LED5-K)") (class "Default")
      (node (ref "LED5") (pin "1") (pinfunction "K_1") (pintype "passive"))
      (node (ref "U2") (pin "12") (pinfunction "6Y_12") (pintype "passive"))
    )
    (net (code "40") (name "Net-(LED6-A)") (class "Default")
      (node (ref "LED6") (pin "2") (pinfunction "A_2") (pintype "passive"))
      (node (ref "R85") (pin "1") (pinfunction "1_1") (pintype "passive"))
    )
    (net (code "41") (name "Net-(LED6-K)") (class "Default")
      (node (ref "LED6") (pin "1") (pinfunction "K_1") (pintype "passive"))
      (node (ref "U1") (pin "18") (pinfunction "1Y1_18") (pintype "passive"))
    )
    (net (code "42") (name "Net-(LED7-A)") (class "Default")
      (node (ref "LED7") (pin "2") (pinfunction "A_2") (pintype "passive"))
      (node (ref "R86") (pin "1") (pinfunction "1_1") (pintype "passive"))
    )
    (net (code "43") (name "Net-(LED7-K)") (class "Default")
      (node (ref "LED7") (pin "1") (pinfunction "K_1") (pintype "passive"))
      (node (ref "U1") (pin "16") (pinfunction "1Y2_16") (pintype "passive"))
    )
    (net (code "44") (name "Net-(LED8-A)") (class "Default")
      (node (ref "LED8") (pin "2") (pinfunction "A_2") (pintype "passive"))
      (node (ref "R87") (pin "1") (pinfunction "1_1") (pintype "passive"))
    )
    (net (code "45") (name "Net-(LED8-K)") (class "Default")
      (node (ref "LED8") (pin "1") (pinfunction "K_1") (pintype "passive"))
      (node (ref "U1") (pin "14") (pinfunction "1Y3_14") (pintype "passive"))
    )
    (net (code "46") (name "Net-(LED9-A)") (class "Default")
      (node (ref "LED9") (pin "2") (pinfunction "A_2") (pintype "passive"))
      (node (ref "R88") (pin "1") (pinfunction "1_1") (pintype "passive"))
    )
    (net (code "47") (name "Net-(LED9-K)") (class "Default")
      (node (ref "LED9") (pin "1") (pinfunction "K_1") (pintype "passive"))
      (node (ref "U1") (pin "12") (pinfunction "1Y4_12") (pintype "passive"))
    )
    (net (code "48") (name "Net-(LED10-A)") (class "Default")
      (node (ref "LED10") (pin "2") (pinfunction "A_2") (pintype "passive"))
      (node (ref "R89") (pin "1") (pinfunction "1_1") (pintype "passive"))
    )
    (net (code "49") (name "Net-(LED10-K)") (class "Default")
      (node (ref "LED10") (pin "1") (pinfunction "K_1") (pintype "passive"))
      (node (ref "U1") (pin "9") (pinfunction "2Y1_9") (pintype "passive"))
    )
    (net (code "50") (name "Net-(LED11-A)") (class "Default")
      (node (ref "LED11") (pin "2") (pinfunction "A_2") (pintype "passive"))
      (node (ref "R90") (pin "1") (pinfunction "1_1") (pintype "passive"))
    )
    (net (code "51") (name "Net-(LED11-K)") (class "Default")
      (node (ref "LED11") (pin "1") (pinfunction "K_1") (pintype "passive"))
      (node (ref "U1") (pin "7") (pinfunction "2Y2_7") (pintype "passive"))
    )
    (net (code "52") (name "Net-(LED12-A)") (class "Default")
      (node (ref "LED12") (pin "2") (pinfunction "A_2") (pintype "passive"))
      (node (ref "R91") (pin "1") (pinfunction "1_1") (pintype "passive"))
    )
    (net (code "53") (name "Net-(LED12-K)") (class "Default")
      (node (ref "LED12") (pin "1") (pinfunction "K_1") (pintype "passive"))
      (node (ref "U1") (pin "5") (pinfunction "2Y3_5") (pintype "passive"))
    )
    (net (code "54") (name "Net-(LED13-A)") (class "Default")
      (node (ref "LED13") (pin "2") (pinfunction "A_2") (pintype "passive"))
      (node (ref "R92") (pin "1") (pinfunction "1_1") (pintype "passive"))
    )
    (net (code "55") (name "Net-(LED13-K)") (class "Default")
      (node (ref "LED13") (pin "1") (pinfunction "K_1") (pintype "passive"))
      (node (ref "U1") (pin "3") (pinfunction "2Y4_3") (pintype "passive"))
    )
    (net (code "56") (name "Net-(LED14-A)") (class "Default")
      (node (ref "LED14") (pin "2") (pinfunction "A_2") (pintype "passive"))
      (node (ref "R81") (pin "1") (pinfunction "1_1") (pintype "passive"))
    )
    (net (code "57") (name "Net-(LED14-K)") (class "Default")
      (node (ref "LED14") (pin "1") (pinfunction "K_1") (pintype "passive"))
      (node (ref "U2") (pin "10") (pinfunction "5Y_10") (pintype "passive"))
    )
    (net (code "58") (name "Net-(LED15-A)") (class "Default")
      (node (ref "LED15") (pin "2") (pinfunction "A_2") (pintype "passive"))
      (node (ref "R83") (pin "1") (pinfunction "1_1") (pintype "passive"))
    )
    (net (code "59") (name "Net-(LED16-A)") (class "Default")
      (node (ref "LED16") (pin "2") (pinfunction "A_2") (pintype "passive"))
      (node (ref "R84") (pin "2") (pinfunction "2_2") (pintype "passive"))
    )
    (net (code "60") (name "Net-(LED17-A)") (class "Default")
      (node (ref "LED17") (pin "2") (pinfunction "A_2") (pintype "passive"))
      (node (ref "R99") (pin "1") (pinfunction "1_1") (pintype "passive"))
    )
    (net (code "61") (name "Net-(LED17-K)") (class "Default")
      (node (ref "LED17") (pin "1") (pinfunction "K_1") (pintype "passive"))
      (node (ref "R112") (pin "2") (pinfunction "2_2") (pintype "passive"))
    )
    (net (code "62") (name "Net-(LED18-A)") (class "Default")
      (node (ref "LED18") (pin "2") (pinfunction "A_2") (pintype "passive"))
      (node (ref "R100") (pin "2") (pinfunction "2_2") (pintype "passive"))
    )
    (net (code "63") (name "Net-(LED18-K)") (class "Default")
      (node (ref "LED18") (pin "1") (pinfunction "K_1") (pintype "passive"))
      (node (ref "R115") (pin "2") (pinfunction "2_2") (pintype "passive"))
    )
    (net (code "64") (name "Net-(LED19-A)") (class "Default")
      (node (ref "LED19") (pin "2") (pinfunction "A_2") (pintype "passive"))
      (node (ref "R101") (pin "1") (pinfunction "1_1") (pintype "passive"))
    )
    (net (code "65") (name "Net-(LED19-K)") (class "Default")
      (node (ref "LED19") (pin "1") (pinfunction "K_1") (pintype "passive"))
      (node (ref "R118") (pin "2") (pinfunction "2_2") (pintype "passive"))
    )
    (net (code "66") (name "Net-(LED20-A)") (class "Default")
      (node (ref "LED20") (pin "2") (pinfunction "A_2") (pintype "passive"))
      (node (ref "R102") (pin "1") (pinfunction "1_1") (pintype "passive"))
    )
    (net (code "67") (name "Net-(LED20-K)") (class "Default")
      (node (ref "LED20") (pin "1") (pinfunction "K_1") (pintype "passive"))
      (node (ref "R121") (pin "2") (pinfunction "2_2") (pintype "passive"))
    )
    (net (code "68") (name "Net-(LED21-A)") (class "Default")
      (node (ref "LED21") (pin "2") (pinfunction "A_2") (pintype "passive"))
      (node (ref "R103") (pin "1") (pinfunction "1_1") (pintype "passive"))
    )
    (net (code "69") (name "Net-(LED21-K)") (class "Default")
      (node (ref "LED21") (pin "1") (pinfunction "K_1") (pintype "passive"))
      (node (ref "R124") (pin "2") (pinfunction "2_2") (pintype "passive"))
    )
    (net (code "70") (name "Net-(LED22-A)") (class "Default")
      (node (ref "LED22") (pin "2") (pinfunction "A_2") (pintype "passive"))
      (node (ref "R104") (pin "1") (pinfunction "1_1") (pintype "passive"))
    )
    (net (code "71") (name "Net-(LED22-K)") (class "Default")
      (node (ref "LED22") (pin "1") (pinfunction "K_1") (pintype "passive"))
      (node (ref "U3") (pin "2") (pinfunction "1Y_2") (pintype "passive"))
    )
    (net (code "72") (name "Net-(LED23-A)") (class "Default")
      (node (ref "LED23") (pin "2") (pinfunction "A_2") (pintype "passive"))
      (node (ref "R105") (pin "1") (pinfunction "1_1") (pintype "passive"))
    )
    (net (code "73") (name "Net-(LED23-K)") (class "Default")
      (node (ref "LED23") (pin "1") (pinfunction "K_1") (pintype "passive"))
      (node (ref "U3") (pin "4") (pinfunction "2Y_4") (pintype "passive"))
    )
    (net (code "74") (name "Net-(LED24-A)") (class "Default")
      (node (ref "LED24") (pin "2") (pinfunction "A_2") (pintype "passive"))
      (node (ref "R106") (pin "1") (pinfunction "1_1") (pintype "passive"))
    )
    (net (code "75") (name "Net-(LED24-K)") (class "Default")
      (node (ref "LED24") (pin "1") (pinfunction "K_1") (pintype "passive"))
      (node (ref "U3") (pin "6") (pinfunction "3Y_6") (pintype "passive"))
    )
    (net (code "76") (name "Net-(LED25-A)") (class "Default")
      (node (ref "LED25") (pin "2") (pinfunction "A_2") (pintype "passive"))
      (node (ref "R107") (pin "1") (pinfunction "1_1") (pintype "passive"))
    )
    (net (code "77") (name "Net-(LED25-K)") (class "Default")
      (node (ref "LED25") (pin "1") (pinfunction "K_1") (pintype "passive"))
      (node (ref "U3") (pin "8") (pinfunction "4Y_8") (pintype "passive"))
    )
    (net (code "78") (name "Net-(LED26-A)") (class "Default")
      (node (ref "LED26") (pin "2") (pinfunction "A_2") (pintype "passive"))
      (node (ref "R108") (pin "1") (pinfunction "1_1") (pintype "passive"))
    )
    (net (code "79") (name "Net-(LED26-K)") (class "Default")
      (node (ref "LED26") (pin "1") (pinfunction "K_1") (pintype "passive"))
      (node (ref "U3") (pin "10") (pinfunction "5Y_10") (pintype "passive"))
    )
    (net (code "80") (name "Net-(LED27-A)") (class "Default")
      (node (ref "LED27") (pin "2") (pinfunction "A_2") (pintype "passive"))
      (node (ref "R109") (pin "1") (pinfunction "1_1") (pintype "passive"))
    )
    (net (code "81") (name "Net-(LED27-K)") (class "Default")
      (node (ref "LED27") (pin "1") (pinfunction "K_1") (pintype "passive"))
      (node (ref "U3") (pin "12") (pinfunction "6Y_12") (pintype "passive"))
    )
    (net (code "82") (name "Net-(LED28-A)") (class "Default")
      (node (ref "LED28") (pin "2") (pinfunction "A_2") (pintype "passive"))
      (node (ref "R110") (pin "1") (pinfunction "1_1") (pintype "passive"))
    )
    (net (code "83") (name "Net-(LED28-K)") (class "Default")
      (node (ref "LED28") (pin "1") (pinfunction "K_1") (pintype "passive"))
      (node (ref "U4") (pin "2") (pinfunction "1Y_2") (pintype "passive"))
    )
    (net (code "84") (name "Net-(LED29-A)") (class "Default")
      (node (ref "LED29") (pin "2") (pinfunction "A_2") (pintype "passive"))
      (node (ref "R111") (pin "1") (pinfunction "1_1") (pintype "passive"))
    )
    (net (code "85") (name "Net-(LED29-K)") (class "Default")
      (node (ref "LED29") (pin "1") (pinfunction "K_1") (pintype "passive"))
      (node (ref "U4") (pin "4") (pinfunction "2Y_4") (pintype "passive"))
    )
    (net (code "86") (name "Net-(R120-Pad1)") (class "Default")
      (node (ref "R120") (pin "1") (pinfunction "1_1") (pintype "passive"))
      (node (ref "TP8") (pin "1") (pinfunction "1_1") (pintype "passive"))
    )
    (net (code "87") (name "Net-(R123-Pad1)") (class "Default")
      (node (ref "R123") (pin "1") (pinfunction "1_1") (pintype "passive"))
      (node (ref "TP10") (pin "1") (pinfunction "1_1") (pintype "passive"))
    )
    (net (code "88") (name "Net-(R126-Pad1)") (class "Default")
      (node (ref "R126") (pin "1") (pinfunction "1_1") (pintype "passive"))
      (node (ref "TP12") (pin "1") (pinfunction "1_1") (pintype "passive"))
    )
    (net (code "89") (name "Net-(R128-Pad1)") (class "Default")
      (node (ref "R128") (pin "1") (pinfunction "1_1") (pintype "passive"))
      (node (ref "TP14") (pin "1") (pinfunction "1_1") (pintype "passive"))
    )
    (net (code "90") (name "Net-(U2-1A)") (class "Default")
      (node (ref "R93") (pin "2") (pinfunction "2_2") (pintype "passive"))
      (node (ref "U2") (pin "1") (pinfunction "1A_1") (pintype "passive"))
    )
    (net (code "91") (name "Net-(U2-2A)") (class "Default")
      (node (ref "R94") (pin "2") (pinfunction "2_2") (pintype "passive"))
      (node (ref "U2") (pin "3") (pinfunction "2A_3") (pintype "passive"))
    )
    (net (code "92") (name "Net-(U2-3A)") (class "Default")
      (node (ref "R95") (pin "2") (pinfunction "2_2") (pintype "passive"))
      (node (ref "U2") (pin "5") (pinfunction "3A_5") (pintype "passive"))
    )
    (net (code "93") (name "Net-(U2-4A)") (class "Default")
      (node (ref "R96") (pin "2") (pinfunction "2_2") (pintype "passive"))
      (node (ref "U2") (pin "9") (pinfunction "4A_9") (pintype "passive"))
    )
    (net (code "94") (name "Net-(U2-5A)") (class "Default")
      (node (ref "R97") (pin "2") (pinfunction "2_2") (pintype "passive"))
      (node (ref "U2") (pin "11") (pinfunction "5A_11") (pintype "passive"))
    )
    (net (code "95") (name "Net-(U2-6A)") (class "Default")
      (node (ref "R98") (pin "2") (pinfunction "2_2") (pintype "passive"))
      (node (ref "U2") (pin "13") (pinfunction "6A_13") (pintype "passive"))
    )
    (net (code "96") (name "Net-(U3-1A)") (class "Default")
      (node (ref "R113") (pin "2") (pinfunction "2_2") (pintype "passive"))
      (node (ref "U3") (pin "1") (pinfunction "1A_1") (pintype "passive"))
    )
    (net (code "97") (name "Net-(U3-2A)") (class "Default")
      (node (ref "R116") (pin "2") (pinfunction "2_2") (pintype "passive"))
      (node (ref "U3") (pin "3") (pinfunction "2A_3") (pintype "passive"))
    )
    (net (code "98") (name "Net-(U3-3A)") (class "Default")
      (node (ref "R119") (pin "2") (pinfunction "2_2") (pintype "passive"))
      (node (ref "U3") (pin "5") (pinfunction "3A_5") (pintype "passive"))
    )
    (net (code "99") (name "Net-(U3-4A)") (class "Default")
      (node (ref "R122") (pin "2") (pinfunction "2_2") (pintype "passive"))
      (node (ref "U3") (pin "9") (pinfunction "4A_9") (pintype "passive"))
    )
    (net (code "100") (name "Net-(U3-5A)") (class "Default")
      (node (ref "R125") (pin "2") (pinfunction "2_2") (pintype "passive"))
      (node (ref "U3") (pin "11") (pinfunction "5A_11") (pintype "passive"))
    )
    (net (code "101") (name "Net-(U3-6A)") (class "Default")
      (node (ref "R127") (pin "2") (pinfunction "2_2") (pintype "passive"))
      (node (ref "U3") (pin "13") (pinfunction "6A_13") (pintype "passive"))
    )
    (net (code "102") (name "Net-(U4-1A)") (class "Default")
      (node (ref "R114") (pin "2") (pinfunction "2_2") (pintype "passive"))
      (node (ref "U4") (pin "1") (pinfunction "1A_1") (pintype "passive"))
    )
    (net (code "103") (name "Net-(U4-2A)") (class "Default")
      (node (ref "R117") (pin "2") (pinfunction "2_2") (pintype "passive"))
      (node (ref "U4") (pin "3") (pinfunction "2A_3") (pintype "passive"))
    )
    (net (code "104") (name "Net-(U4-3A)") (class "Default")
      (node (ref "R120") (pin "2") (pinfunction "2_2") (pintype "passive"))
      (node (ref "U4") (pin "5") (pinfunction "3A_5") (pintype "passive"))
    )
    (net (code "105") (name "Net-(U4-3Y)") (class "Default")
      (node (ref "TP9") (pin "1") (pinfunction "1_1") (pintype "passive"))
      (node (ref "U4") (pin "6") (pinfunction "3Y_6") (pintype "passive"))
    )
    (net (code "106") (name "Net-(U4-4A)") (class "Default")
      (node (ref "R123") (pin "2") (pinfunction "2_2") (pintype "passive"))
      (node (ref "U4") (pin "9") (pinfunction "4A_9") (pintype "passive"))
    )
    (net (code "107") (name "Net-(U4-4Y)") (class "Default")
      (node (ref "TP11") (pin "1") (pinfunction "1_1") (pintype "passive"))
      (node (ref "U4") (pin "8") (pinfunction "4Y_8") (pintype "passive"))
    )
    (net (code "108") (name "Net-(U4-5A)") (class "Default")
      (node (ref "R126") (pin "2") (pinfunction "2_2") (pintype "passive"))
      (node (ref "U4") (pin "11") (pinfunction "5A_11") (pintype "passive"))
    )
    (net (code "109") (name "Net-(U4-5Y)") (class "Default")
      (node (ref "TP13") (pin "1") (pinfunction "1_1") (pintype "passive"))
      (node (ref "U4") (pin "10") (pinfunction "5Y_10") (pintype "passive"))
    )
    (net (code "110") (name "Net-(U4-6A)") (class "Default")
      (node (ref "R128") (pin "2") (pinfunction "2_2") (pintype "passive"))
      (node (ref "U4") (pin "13") (pinfunction "6A_13") (pintype "passive"))
    )
    (net (code "111") (name "Net-(U4-6Y)") (class "Default")
      (node (ref "TP15") (pin "1") (pinfunction "1_1") (pintype "passive"))
      (node (ref "U4") (pin "12") (pinfunction "6Y_12") (pintype "passive"))
    )
  )
)
